# 11_-Power_Input_and_Regulators.net
KiCad netlist of a schematic drawn in Altium Designer
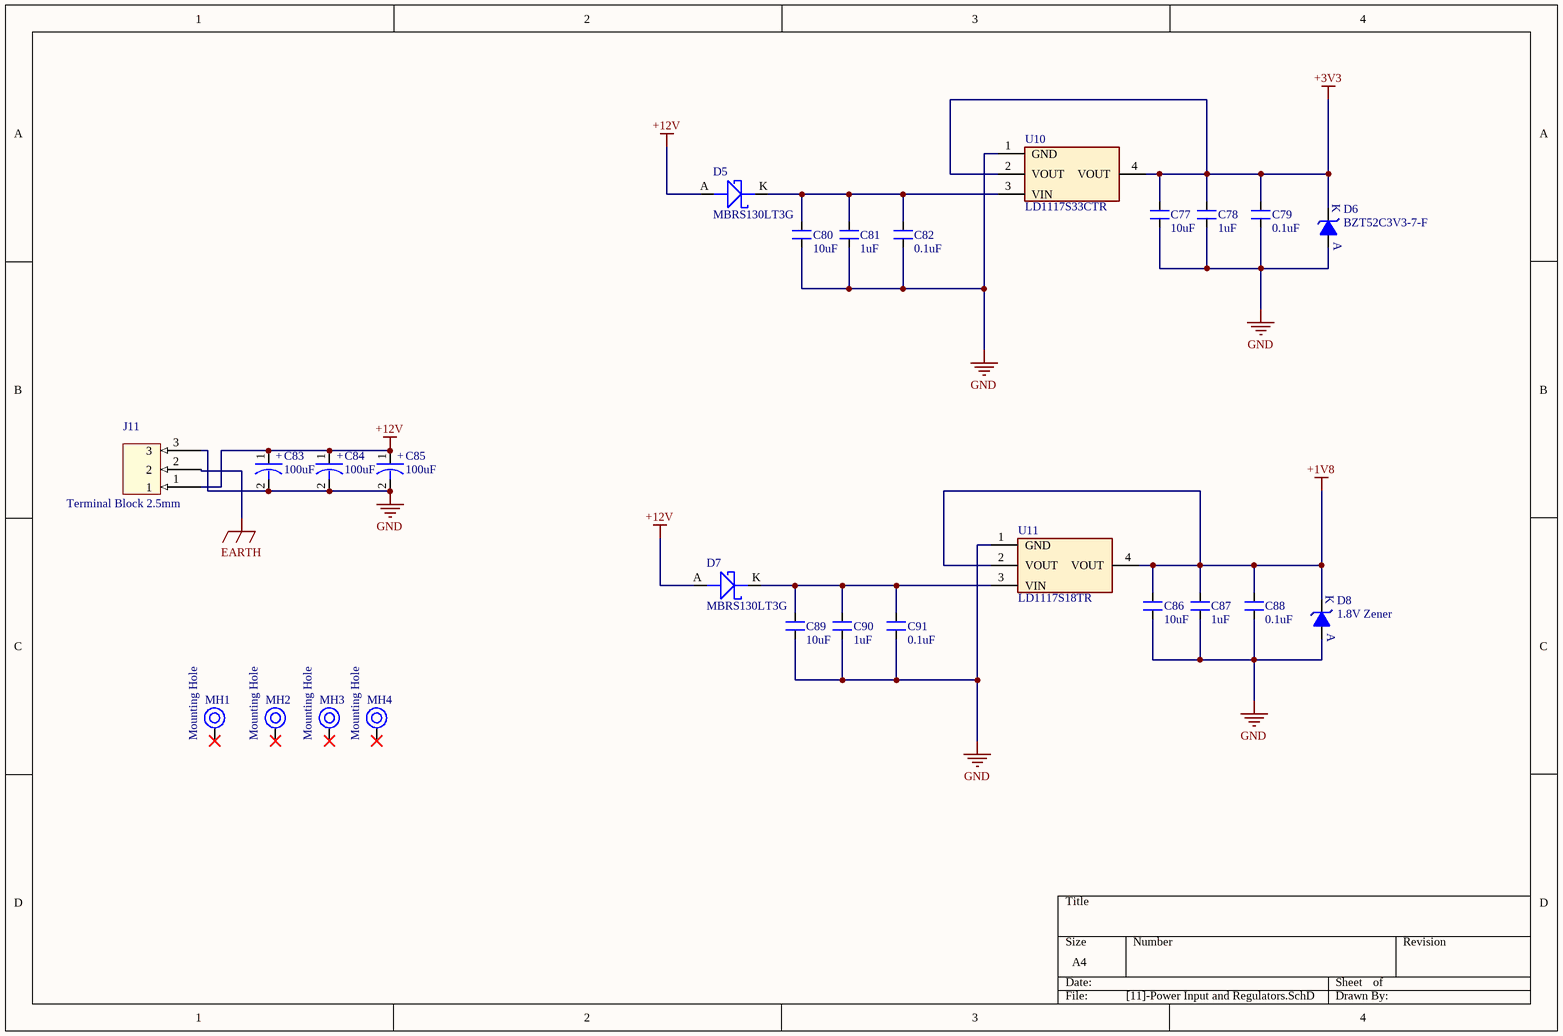
[diagram p0: [11]-Power Input and Regulators.SchDoc]

(export (version "E")
  (design (tool "Eeschema 10.0.6"))
  (components
    (comp (ref "C77")
      (value "10uF")
      (footprint "CAP_1206")
      (description "10µF ±10% 50V Ceramic Capacitor X7R 1206 (3216 Metric)")
      (fields
        (field (name "MANUFACTURER") "KEMET")
        (field (name "MANUFACTURER PART NUMBER") "CL31B106KBHNNNE")
      )
      (libsource (lib "ESTEEMPCBLIB") (part "CAP_10uF-50V-10%-1206"))
    )
    (comp (ref "C78")
      (value "1uF")
      (footprint "CAP_0805")
      (description "1µF ±5% 50V Ceramic Capacitor X7R 0805 (2012 Metric)")
      (fields
        (field (name "MANUFACTURER") "Samsung")
        (field (name "MANUFACTURER PART NUMBER") "CC0805JKX7R9BB105")
      )
      (libsource (lib "ESTEEMPCBLIB") (part "CAP_1uF-50V-5%-0805"))
    )
    (comp (ref "C79")
      (value "0.1uF")
      (footprint "CAP_0805")
      (description "0.1µF ±10% 50V Ceramic Capacitor X7R 0805 (2012 Metric)")
      (fields
        (field (name "MANUFACTURER") "Samsung")
        (field (name "MANUFACTURER PART NUMBER") "CL21B104KBCNNNC")
      )
      (libsource (lib "ESTEEMPCBLIB") (part "CAP_0.1uF-50V-10%-0805"))
    )
    (comp (ref "C80")
      (value "10uF")
      (footprint "CAP_1206")
      (description "10µF ±10% 50V Ceramic Capacitor X7R 1206 (3216 Metric)")
      (fields
        (field (name "MANUFACTURER") "KEMET")
        (field (name "MANUFACTURER PART NUMBER") "CL31B106KBHNNNE")
      )
      (libsource (lib "ESTEEMPCBLIB") (part "CAP_10uF-50V-10%-1206"))
    )
    (comp (ref "C81")
      (value "1uF")
      (footprint "CAP_0805")
      (description "1µF ±5% 50V Ceramic Capacitor X7R 0805 (2012 Metric)")
      (fields
        (field (name "MANUFACTURER") "Samsung")
        (field (name "MANUFACTURER PART NUMBER") "CC0805JKX7R9BB105")
      )
      (libsource (lib "ESTEEMPCBLIB") (part "CAP_1uF-50V-5%-0805"))
    )
    (comp (ref "C82")
      (value "0.1uF")
      (footprint "CAP_0805")
      (description "0.1µF ±10% 50V Ceramic Capacitor X7R 0805 (2012 Metric)")
      (fields
        (field (name "MANUFACTURER") "Samsung")
        (field (name "MANUFACTURER PART NUMBER") "CL21B104KBCNNNC")
      )
      (libsource (lib "ESTEEMPCBLIB") (part "CAP_0.1uF-50V-10%-0805"))
    )
    (comp (ref "C83")
      (value "100uF")
      (footprint "ACAP_P305_D393_H393_RAD")
      (description "100µF 50V Aluminum Polymer Capacitor Radial, Can - SMD 28mOhm 4000 Hrs @ 125°C")
      (fields
        (field (name "MANUFACTURER") "Nichicon")
        (field (name "MANUFACTURER PART NUMBER") "GYA1H101MCQ1GS")
      )
      (libsource (lib "ESTEEMPCBLIB") (part "CAP-P_100uF-50V-20%-RAD"))
    )
    (comp (ref "C84")
      (value "100uF")
      (footprint "ACAP_P305_D393_H393_RAD")
      (description "100µF 50V Aluminum Polymer Capacitor Radial, Can - SMD 28mOhm 4000 Hrs @ 125°C")
      (fields
        (field (name "MANUFACTURER") "Nichicon")
        (field (name "MANUFACTURER PART NUMBER") "GYA1H101MCQ1GS")
      )
      (libsource (lib "ESTEEMPCBLIB") (part "CAP-P_100uF-50V-20%-RAD"))
    )
    (comp (ref "C85")
      (value "100uF")
      (footprint "ACAP_P305_D393_H393_RAD")
      (description "100µF 50V Aluminum Polymer Capacitor Radial, Can - SMD 28mOhm 4000 Hrs @ 125°C")
      (fields
        (field (name "MANUFACTURER") "Nichicon")
        (field (name "MANUFACTURER PART NUMBER") "GYA1H101MCQ1GS")
      )
      (libsource (lib "ESTEEMPCBLIB") (part "CAP-P_100uF-50V-20%-RAD"))
    )
    (comp (ref "C86")
      (value "10uF")
      (footprint "CAP_1206")
      (description "10µF ±10% 50V Ceramic Capacitor X7R 1206 (3216 Metric)")
      (fields
        (field (name "MANUFACTURER") "KEMET")
        (field (name "MANUFACTURER PART NUMBER") "CL31B106KBHNNNE")
      )
      (libsource (lib "ESTEEMPCBLIB") (part "CAP_10uF-50V-10%-1206"))
    )
    (comp (ref "C87")
      (value "1uF")
      (footprint "CAP_0805")
      (description "1µF ±5% 50V Ceramic Capacitor X7R 0805 (2012 Metric)")
      (fields
        (field (name "MANUFACTURER") "Samsung")
        (field (name "MANUFACTURER PART NUMBER") "CC0805JKX7R9BB105")
      )
      (libsource (lib "ESTEEMPCBLIB") (part "CAP_1uF-50V-5%-0805"))
    )
    (comp (ref "C88")
      (value "0.1uF")
      (footprint "CAP_0805")
      (description "0.1µF ±10% 50V Ceramic Capacitor X7R 0805 (2012 Metric)")
      (fields
        (field (name "MANUFACTURER") "Samsung")
        (field (name "MANUFACTURER PART NUMBER") "CL21B104KBCNNNC")
      )
      (libsource (lib "ESTEEMPCBLIB") (part "CAP_0.1uF-50V-10%-0805"))
    )
    (comp (ref "C89")
      (value "10uF")
      (footprint "CAP_1206")
      (description "10µF ±10% 50V Ceramic Capacitor X7R 1206 (3216 Metric)")
      (fields
        (field (name "MANUFACTURER") "KEMET")
        (field (name "MANUFACTURER PART NUMBER") "CL31B106KBHNNNE")
      )
      (libsource (lib "ESTEEMPCBLIB") (part "CAP_10uF-50V-10%-1206"))
    )
    (comp (ref "C90")
      (value "1uF")
      (footprint "CAP_0805")
      (description "1µF ±5% 50V Ceramic Capacitor X7R 0805 (2012 Metric)")
      (fields
        (field (name "MANUFACTURER") "Samsung")
        (field (name "MANUFACTURER PART NUMBER") "CC0805JKX7R9BB105")
      )
      (libsource (lib "ESTEEMPCBLIB") (part "CAP_1uF-50V-5%-0805"))
    )
    (comp (ref "C91")
      (value "0.1uF")
      (footprint "CAP_0805")
      (description "0.1µF ±10% 50V Ceramic Capacitor X7R 0805 (2012 Metric)")
      (fields
        (field (name "MANUFACTURER") "Samsung")
        (field (name "MANUFACTURER PART NUMBER") "CL21B104KBCNNNC")
      )
      (libsource (lib "ESTEEMPCBLIB") (part "CAP_0.1uF-50V-10%-0805"))
    )
    (comp (ref "D5")
      (value "MBRS130LT3G")
      (footprint "DIO_SMB_DO-214AA")
      (description "Diode Schottky 30V 2A Surface Mount SMB")
      (fields (field (name "MANUFACTURER") "ON Semiconductor"))
      (libsource (lib "ESTEEMPCBLIB") (part "DIO-S_445mV-30V-2A-SMB"))
    )
    (comp (ref "D6")
      (value "BZT52C3V3-7-F")
      (footprint "DIO_SOD-123")
      (description "Zener Diode 3.3V 500mW ±6% Surface Mount SOD-123")
      (fields (field (name "MANUFACTURER") "Diodes Incorporated"))
      (libsource (lib "ESTEEMPCBLIB") (part "DIO-Z_3.3V-500mW-SOD123"))
    )
    (comp (ref "D7")
      (value "MBRS130LT3G")
      (footprint "DIO_SMB_DO-214AA")
      (description "Diode Schottky 30V 2A Surface Mount SMB")
      (fields (field (name "MANUFACTURER") "ON Semiconductor"))
      (libsource (lib "ESTEEMPCBLIB") (part "DIO-S_445mV-30V-2A-SMB"))
    )
    (comp (ref "D8")
      (value "1.8V Zener")
      (footprint "DIO_DO-213AB_SMD")
      (description "Zener Diode 1.8V 500mW ±5% Surface Mount DO-213AA")
      (libsource (lib "ESTEEMPCBLIB") (part "DIO-Z_1.8V-500mW-DO213AA"))
    )
    (comp (ref "J11")
      (value "Terminal Block 2.5mm")
      (footprint "CON3_100_TB_TH_ST")
      (description "3 Pins, 1 Row 2.54mm Pitch, straight Connector, male")
      (fields
        (field (name "MANUFACTURER PART NUMBER") "1725669")
        (field (name "MANUFACTURER") "Phoenix Contact")
      )
      (libsource (lib "ESTEEMPCBLIB") (part "CON-TB_3X1-100-ST-TH"))
    )
    (comp (ref "MH1")
      (value "Mounting Hole")
      (footprint "MOUNTING")
      (fields (field (name "MANUFACTURER PART NUMBER") "NA"))
      (libsource (lib "ESTEEMPCBLIB") (part "MH_3.5H_6D"))
    )
    (comp (ref "MH2")
      (value "Mounting Hole")
      (footprint "MOUNTING")
      (fields (field (name "MANUFACTURER PART NUMBER") "NA"))
      (libsource (lib "ESTEEMPCBLIB") (part "MH_3.5H_6D"))
    )
    (comp (ref "MH3")
      (value "Mounting Hole")
      (footprint "MOUNTING")
      (fields (field (name "MANUFACTURER PART NUMBER") "NA"))
      (libsource (lib "ESTEEMPCBLIB") (part "MH_3.5H_6D"))
    )
    (comp (ref "MH4")
      (value "Mounting Hole")
      (footprint "MOUNTING")
      (fields (field (name "MANUFACTURER PART NUMBER") "NA"))
      (libsource (lib "ESTEEMPCBLIB") (part "MH_3.5H_6D"))
    )
    (comp (ref "U10")
      (value "LD1117S33CTR")
      (footprint "SOT223_3")
      (description "Linear Voltage Regulator IC 1 Output 800mA SOT-223")
      (fields (field (name "MANUFACTURER") "STMicroelectronics"))
      (libsource (lib "ESTEEMPCBLIB") (part "REG_15V-3.3V-0.9A-12W-SOT223"))
    )
    (comp (ref "U11")
      (value "LD1117S18TR")
      (footprint "SOT223_3")
      (description "LDO Voltage Regulators 1.8V 0.8A Positive")
      (fields (field (name "MANUFACTURER") "STMicroelectronics"))
      (libsource (lib "ESTEEMPCBLIB") (part "REG_15V-1.8V-0.8A-1.4W-SOT223"))
    )
  )
  (nets
    (net (code "1") (name "+1V8") (class "Default")
      (node (ref "C86") (pin "2") (pinfunction "2_2") (pintype "passive"))
      (node (ref "C87") (pin "2") (pinfunction "2_2") (pintype "passive"))
      (node (ref "C88") (pin "2") (pinfunction "2_2") (pintype "passive"))
      (node (ref "D8") (pin "K") (pinfunction "K_K") (pintype "passive"))
      (node (ref "U11") (pin "2") (pinfunction "VOUT_2") (pintype "passive"))
      (node (ref "U11") (pin "4") (pinfunction "VOUT_4") (pintype "passive"))
    )
    (net (code "2") (name "+3V3") (class "Default")
      (node (ref "C77") (pin "2") (pinfunction "2_2") (pintype "passive"))
      (node (ref "C78") (pin "2") (pinfunction "2_2") (pintype "passive"))
      (node (ref "C79") (pin "2") (pinfunction "2_2") (pintype "passive"))
      (node (ref "D6") (pin "K") (pinfunction "K_K") (pintype "passive"))
      (node (ref "U10") (pin "2") (pinfunction "VOUT_2") (pintype "passive"))
      (node (ref "U10") (pin "4") (pinfunction "VOUT_4") (pintype "passive"))
    )
    (net (code "3") (name "+12V") (class "Default")
      (node (ref "C83") (pin "1") (pinfunction "1_1") (pintype "passive"))
      (node (ref "C84") (pin "1") (pinfunction "1_1") (pintype "passive"))
      (node (ref "C85") (pin "1") (pinfunction "1_1") (pintype "passive"))
      (node (ref "D5") (pin "A") (pinfunction "A_A") (pintype "passive"))
      (node (ref "D7") (pin "A") (pinfunction "A_A") (pintype "passive"))
      (node (ref "J11") (pin "1") (pinfunction "1_1") (pintype "input"))
    )
    (net (code "4") (name "EARTH") (class "Default")
      (node (ref "J11") (pin "2") (pinfunction "2_2") (pintype "input"))
    )
    (net (code "5") (name "GND") (class "Default")
      (node (ref "C77") (pin "1") (pinfunction "1_1") (pintype "passive"))
      (node (ref "C78") (pin "1") (pinfunction "1_1") (pintype "passive"))
      (node (ref "C79") (pin "1") (pinfunction "1_1") (pintype "passive"))
      (node (ref "C80") (pin "1") (pinfunction "1_1") (pintype "passive"))
      (node (ref "C81") (pin "1") (pinfunction "1_1") (pintype "passive"))
      (node (ref "C82") (pin "1") (pinfunction "1_1") (pintype "passive"))
      (node (ref "C83") (pin "2") (pinfunction "2_2") (pintype "passive"))
      (node (ref "C84") (pin "2") (pinfunction "2_2") (pintype "passive"))
      (node (ref "C85") (pin "2") (pinfunction "2_2") (pintype "passive"))
      (node (ref "C86") (pin "1") (pinfunction "1_1") (pintype "passive"))
      (node (ref "C87") (pin "1") (pinfunction "1_1") (pintype "passive"))
      (node (ref "C88") (pin "1") (pinfunction "1_1") (pintype "passive"))
      (node (ref "C89") (pin "1") (pinfunction "1_1") (pintype "passive"))
      (node (ref "C90") (pin "1") (pinfunction "1_1") (pintype "passive"))
      (node (ref "C91") (pin "1") (pinfunction "1_1") (pintype "passive"))
      (node (ref "D6") (pin "A") (pinfunction "A_A") (pintype "passive"))
      (node (ref "D8") (pin "A") (pinfunction "A_A") (pintype "passive"))
      (node (ref "J11") (pin "3") (pinfunction "3_3") (pintype "input"))
      (node (ref "U10") (pin "1") (pinfunction "GND_1") (pintype "passive"))
      (node (ref "U11") (pin "1") (pinfunction "GND_1") (pintype "passive"))
    )
    (net (code "6") (name "Net-(U10-VIN)") (class "Default")
      (node (ref "C80") (pin "2") (pinfunction "2_2") (pintype "passive"))
      (node (ref "C81") (pin "2") (pinfunction "2_2") (pintype "passive"))
      (node (ref "C82") (pin "2") (pinfunction "2_2") (pintype "passive"))
      (node (ref "D5") (pin "K") (pinfunction "K_K") (pintype "passive"))
      (node (ref "U10") (pin "3") (pinfunction "VIN_3") (pintype "passive"))
    )
    (net (code "7") (name "Net-(U11-VIN)") (class "Default")
      (node (ref "C89") (pin "2") (pinfunction "2_2") (pintype "passive"))
      (node (ref "C90") (pin "2") (pinfunction "2_2") (pintype "passive"))
      (node (ref "C91") (pin "2") (pinfunction "2_2") (pintype "passive"))
      (node (ref "D7") (pin "K") (pinfunction "K_K") (pintype "passive"))
      (node (ref "U11") (pin "3") (pinfunction "VIN_3") (pintype "passive"))
    )
    (net (code "8") (name "unconnected-(MH1-Pad1)") (class "Default")
      (node (ref "MH1") (pin "1") (pinfunction "1_1") (pintype "passive+no_connect"))
    )
    (net (code "9") (name "unconnected-(MH2-Pad1)") (class "Default")
      (node (ref "MH2") (pin "1") (pinfunction "1_1") (pintype "passive+no_connect"))
    )
    (net (code "10") (name "unconnected-(MH3-Pad1)") (class "Default")
      (node (ref "MH3") (pin "1") (pinfunction "1_1") (pintype "passive+no_connect"))
    )
    (net (code "11") (name "unconnected-(MH4-Pad1)") (class "Default")
      (node (ref "MH4") (pin "1") (pinfunction "1_1") (pintype "passive+no_connect"))
    )
  )
)
